# Input.net
KiCad netlist of a schematic drawn in Altium Designer
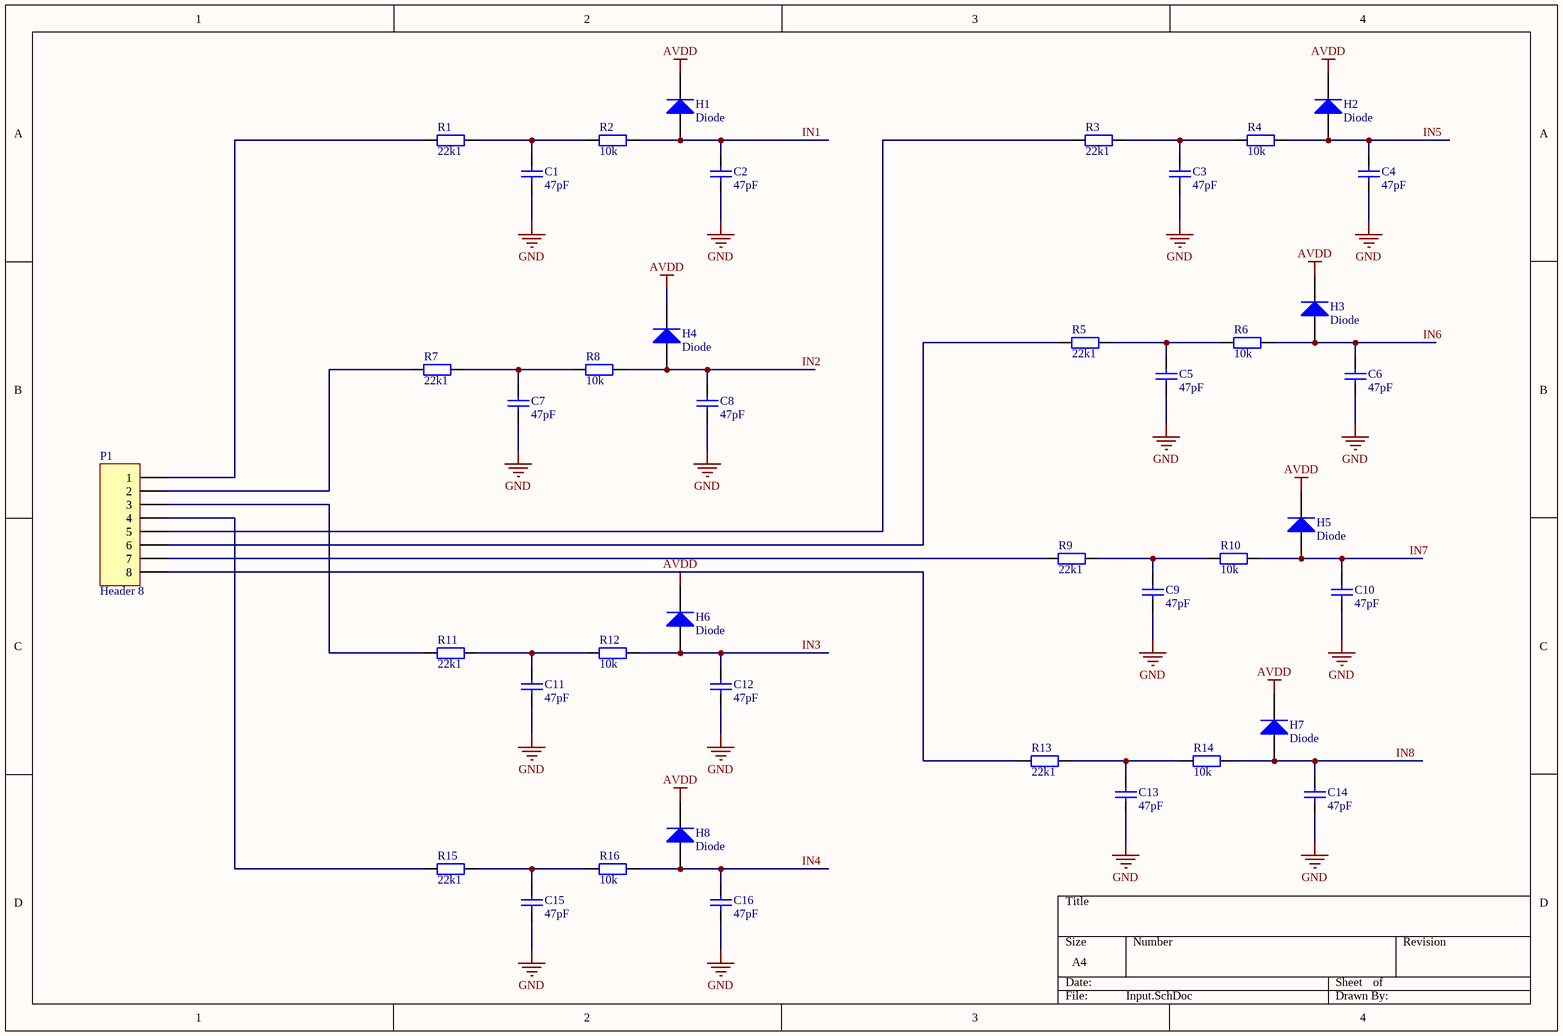
[diagram p0: Input.SchDoc]

(export (version "E")
  (design (tool "Eeschema 10.0.6"))
  (components
    (comp (ref "C1")
      (value "47pF")
      (footprint "RAD-0.3")
      (description "Capacitor")
      (fields (field (name "PUBLISHER") "Altium Limited"))
      (libsource (lib "Miscellaneous Devices") (part "Cap"))
    )
    (comp (ref "C2")
      (value "47pF")
      (footprint "RAD-0.3")
      (description "Capacitor")
      (fields (field (name "PUBLISHER") "Altium Limited"))
      (libsource (lib "Miscellaneous Devices") (part "Cap"))
    )
    (comp (ref "C3")
      (value "47pF")
      (footprint "RAD-0.3")
      (description "Capacitor")
      (fields (field (name "PUBLISHER") "Altium Limited"))
      (libsource (lib "Miscellaneous Devices") (part "Cap"))
    )
    (comp (ref "C4")
      (value "47pF")
      (footprint "RAD-0.3")
      (description "Capacitor")
      (fields (field (name "PUBLISHER") "Altium Limited"))
      (libsource (lib "Miscellaneous Devices") (part "Cap"))
    )
    (comp (ref "C5")
      (value "47pF")
      (footprint "RAD-0.3")
      (description "Capacitor")
      (fields (field (name "PUBLISHER") "Altium Limited"))
      (libsource (lib "Miscellaneous Devices") (part "Cap"))
    )
    (comp (ref "C6")
      (value "47pF")
      (footprint "RAD-0.3")
      (description "Capacitor")
      (fields (field (name "PUBLISHER") "Altium Limited"))
      (libsource (lib "Miscellaneous Devices") (part "Cap"))
    )
    (comp (ref "C7")
      (value "47pF")
      (footprint "RAD-0.3")
      (description "Capacitor")
      (fields (field (name "PUBLISHER") "Altium Limited"))
      (libsource (lib "Miscellaneous Devices") (part "Cap"))
    )
    (comp (ref "C8")
      (value "47pF")
      (footprint "RAD-0.3")
      (description "Capacitor")
      (fields (field (name "PUBLISHER") "Altium Limited"))
      (libsource (lib "Miscellaneous Devices") (part "Cap"))
    )
    (comp (ref "C9")
      (value "47pF")
      (footprint "RAD-0.3")
      (description "Capacitor")
      (fields (field (name "PUBLISHER") "Altium Limited"))
      (libsource (lib "Miscellaneous Devices") (part "Cap"))
    )
    (comp (ref "C10")
      (value "47pF")
      (footprint "RAD-0.3")
      (description "Capacitor")
      (fields (field (name "PUBLISHER") "Altium Limited"))
      (libsource (lib "Miscellaneous Devices") (part "Cap"))
    )
    (comp (ref "C11")
      (value "47pF")
      (footprint "RAD-0.3")
      (description "Capacitor")
      (fields (field (name "PUBLISHER") "Altium Limited"))
      (libsource (lib "Miscellaneous Devices") (part "Cap"))
    )
    (comp (ref "C12")
      (value "47pF")
      (footprint "RAD-0.3")
      (description "Capacitor")
      (fields (field (name "PUBLISHER") "Altium Limited"))
      (libsource (lib "Miscellaneous Devices") (part "Cap"))
    )
    (comp (ref "C13")
      (value "47pF")
      (footprint "RAD-0.3")
      (description "Capacitor")
      (fields (field (name "PUBLISHER") "Altium Limited"))
      (libsource (lib "Miscellaneous Devices") (part "Cap"))
    )
    (comp (ref "C14")
      (value "47pF")
      (footprint "RAD-0.3")
      (description "Capacitor")
      (fields (field (name "PUBLISHER") "Altium Limited"))
      (libsource (lib "Miscellaneous Devices") (part "Cap"))
    )
    (comp (ref "C15")
      (value "47pF")
      (footprint "RAD-0.3")
      (description "Capacitor")
      (fields (field (name "PUBLISHER") "Altium Limited"))
      (libsource (lib "Miscellaneous Devices") (part "Cap"))
    )
    (comp (ref "C16")
      (value "47pF")
      (footprint "RAD-0.3")
      (description "Capacitor")
      (fields (field (name "PUBLISHER") "Altium Limited"))
      (libsource (lib "Miscellaneous Devices") (part "Cap"))
    )
    (comp (ref "H1")
      (value "Diode")
      (footprint "SMC")
      (description "Default Diode")
      (fields (field (name "PUBLISHER") "Altium Limited"))
      (libsource (lib "Miscellaneous Devices") (part "Diode"))
    )
    (comp (ref "H2")
      (value "Diode")
      (footprint "SMC")
      (description "Default Diode")
      (fields (field (name "PUBLISHER") "Altium Limited"))
      (libsource (lib "Miscellaneous Devices") (part "Diode"))
    )
    (comp (ref "H3")
      (value "Diode")
      (footprint "SMC")
      (description "Default Diode")
      (fields (field (name "PUBLISHER") "Altium Limited"))
      (libsource (lib "Miscellaneous Devices") (part "Diode"))
    )
    (comp (ref "H4")
      (value "Diode")
      (footprint "SMC")
      (description "Default Diode")
      (fields (field (name "PUBLISHER") "Altium Limited"))
      (libsource (lib "Miscellaneous Devices") (part "Diode"))
    )
    (comp (ref "H5")
      (value "Diode")
      (footprint "SMC")
      (description "Default Diode")
      (fields (field (name "PUBLISHER") "Altium Limited"))
      (libsource (lib "Miscellaneous Devices") (part "Diode"))
    )
    (comp (ref "H6")
      (value "Diode")
      (footprint "SMC")
      (description "Default Diode")
      (fields (field (name "PUBLISHER") "Altium Limited"))
      (libsource (lib "Miscellaneous Devices") (part "Diode"))
    )
    (comp (ref "H7")
      (value "Diode")
      (footprint "SMC")
      (description "Default Diode")
      (fields (field (name "PUBLISHER") "Altium Limited"))
      (libsource (lib "Miscellaneous Devices") (part "Diode"))
    )
    (comp (ref "H8")
      (value "Diode")
      (footprint "SMC")
      (description "Default Diode")
      (fields (field (name "PUBLISHER") "Altium Limited"))
      (libsource (lib "Miscellaneous Devices") (part "Diode"))
    )
    (comp (ref "P1")
      (value "Header 8")
      (footprint "HDR1X8")
      (description "Header, 8-Pin")
      (fields (field (name "PUBLISHER") "Altium Limited"))
      (libsource (lib "Miscellaneous Connectors") (part "Header 8"))
    )
    (comp (ref "R1")
      (value "22k1")
      (footprint "AXIAL-0.4")
      (description "Resistor")
      (fields (field (name "PUBLISHER") "Altium Limited"))
      (libsource (lib "Miscellaneous Devices") (part "Res2"))
    )
    (comp (ref "R2")
      (value "10k")
      (footprint "AXIAL-0.4")
      (description "Resistor")
      (fields (field (name "PUBLISHER") "Altium Limited"))
      (libsource (lib "Miscellaneous Devices") (part "Res2"))
    )
    (comp (ref "R3")
      (value "22k1")
      (footprint "AXIAL-0.4")
      (description "Resistor")
      (fields (field (name "PUBLISHER") "Altium Limited"))
      (libsource (lib "Miscellaneous Devices") (part "Res2"))
    )
    (comp (ref "R4")
      (value "10k")
      (footprint "AXIAL-0.4")
      (description "Resistor")
      (fields (field (name "PUBLISHER") "Altium Limited"))
      (libsource (lib "Miscellaneous Devices") (part "Res2"))
    )
    (comp (ref "R5")
      (value "22k1")
      (footprint "AXIAL-0.4")
      (description "Resistor")
      (fields (field (name "PUBLISHER") "Altium Limited"))
      (libsource (lib "Miscellaneous Devices") (part "Res2"))
    )
    (comp (ref "R6")
      (value "10k")
      (footprint "AXIAL-0.4")
      (description "Resistor")
      (fields (field (name "PUBLISHER") "Altium Limited"))
      (libsource (lib "Miscellaneous Devices") (part "Res2"))
    )
    (comp (ref "R7")
      (value "22k1")
      (footprint "AXIAL-0.4")
      (description "Resistor")
      (fields (field (name "PUBLISHER") "Altium Limited"))
      (libsource (lib "Miscellaneous Devices") (part "Res2"))
    )
    (comp (ref "R8")
      (value "10k")
      (footprint "AXIAL-0.4")
      (description "Resistor")
      (fields (field (name "PUBLISHER") "Altium Limited"))
      (libsource (lib "Miscellaneous Devices") (part "Res2"))
    )
    (comp (ref "R9")
      (value "22k1")
      (footprint "AXIAL-0.4")
      (description "Resistor")
      (fields (field (name "PUBLISHER") "Altium Limited"))
      (libsource (lib "Miscellaneous Devices") (part "Res2"))
    )
    (comp (ref "R10")
      (value "10k")
      (footprint "AXIAL-0.4")
      (description "Resistor")
      (fields (field (name "PUBLISHER") "Altium Limited"))
      (libsource (lib "Miscellaneous Devices") (part "Res2"))
    )
    (comp (ref "R11")
      (value "22k1")
      (footprint "AXIAL-0.4")
      (description "Resistor")
      (fields (field (name "PUBLISHER") "Altium Limited"))
      (libsource (lib "Miscellaneous Devices") (part "Res2"))
    )
    (comp (ref "R12")
      (value "10k")
      (footprint "AXIAL-0.4")
      (description "Resistor")
      (fields (field (name "PUBLISHER") "Altium Limited"))
      (libsource (lib "Miscellaneous Devices") (part "Res2"))
    )
    (comp (ref "R13")
      (value "22k1")
      (footprint "AXIAL-0.4")
      (description "Resistor")
      (fields (field (name "PUBLISHER") "Altium Limited"))
      (libsource (lib "Miscellaneous Devices") (part "Res2"))
    )
    (comp (ref "R14")
      (value "10k")
      (footprint "AXIAL-0.4")
      (description "Resistor")
      (fields (field (name "PUBLISHER") "Altium Limited"))
      (libsource (lib "Miscellaneous Devices") (part "Res2"))
    )
    (comp (ref "R15")
      (value "22k1")
      (footprint "AXIAL-0.4")
      (description "Resistor")
      (fields (field (name "PUBLISHER") "Altium Limited"))
      (libsource (lib "Miscellaneous Devices") (part "Res2"))
    )
    (comp (ref "R16")
      (value "10k")
      (footprint "AXIAL-0.4")
      (description "Resistor")
      (fields (field (name "PUBLISHER") "Altium Limited"))
      (libsource (lib "Miscellaneous Devices") (part "Res2"))
    )
  )
  (nets
    (net (code "1") (name "/IN1") (class "Default")
      (node (ref "C2") (pin "2") (pinfunction "2_2") (pintype "passive"))
      (node (ref "H1") (pin "1") (pinfunction "A_1") (pintype "passive"))
      (node (ref "R2") (pin "2") (pinfunction "2_2") (pintype "passive"))
    )
    (net (code "2") (name "/IN2") (class "Default")
      (node (ref "C8") (pin "2") (pinfunction "2_2") (pintype "passive"))
      (node (ref "H4") (pin "1") (pinfunction "A_1") (pintype "passive"))
      (node (ref "R8") (pin "2") (pinfunction "2_2") (pintype "passive"))
    )
    (net (code "3") (name "/IN3") (class "Default")
      (node (ref "C12") (pin "2") (pinfunction "2_2") (pintype "passive"))
      (node (ref "H6") (pin "1") (pinfunction "A_1") (pintype "passive"))
      (node (ref "R12") (pin "2") (pinfunction "2_2") (pintype "passive"))
    )
    (net (code "4") (name "/IN4") (class "Default")
      (node (ref "C16") (pin "2") (pinfunction "2_2") (pintype "passive"))
      (node (ref "H8") (pin "1") (pinfunction "A_1") (pintype "passive"))
      (node (ref "R16") (pin "2") (pinfunction "2_2") (pintype "passive"))
    )
    (net (code "5") (name "/IN5") (class "Default")
      (node (ref "C4") (pin "2") (pinfunction "2_2") (pintype "passive"))
      (node (ref "H2") (pin "1") (pinfunction "A_1") (pintype "passive"))
      (node (ref "R4") (pin "2") (pinfunction "2_2") (pintype "passive"))
    )
    (net (code "6") (name "/IN6") (class "Default")
      (node (ref "C6") (pin "2") (pinfunction "2_2") (pintype "passive"))
      (node (ref "H3") (pin "1") (pinfunction "A_1") (pintype "passive"))
      (node (ref "R6") (pin "2") (pinfunction "2_2") (pintype "passive"))
    )
    (net (code "7") (name "/IN7") (class "Default")
      (node (ref "C10") (pin "2") (pinfunction "2_2") (pintype "passive"))
      (node (ref "H5") (pin "1") (pinfunction "A_1") (pintype "passive"))
      (node (ref "R10") (pin "2") (pinfunction "2_2") (pintype "passive"))
    )
    (net (code "8") (name "/IN8") (class "Default")
      (node (ref "C14") (pin "2") (pinfunction "2_2") (pintype "passive"))
      (node (ref "H7") (pin "1") (pinfunction "A_1") (pintype "passive"))
      (node (ref "R14") (pin "2") (pinfunction "2_2") (pintype "passive"))
    )
    (net (code "9") (name "AVDD") (class "Default")
      (node (ref "H1") (pin "2") (pinfunction "K_2") (pintype "passive"))
      (node (ref "H2") (pin "2") (pinfunction "K_2") (pintype "passive"))
      (node (ref "H3") (pin "2") (pinfunction "K_2") (pintype "passive"))
      (node (ref "H4") (pin "2") (pinfunction "K_2") (pintype "passive"))
      (node (ref "H5") (pin "2") (pinfunction "K_2") (pintype "passive"))
      (node (ref "H6") (pin "2") (pinfunction "K_2") (pintype "passive"))
      (node (ref "H7") (pin "2") (pinfunction "K_2") (pintype "passive"))
      (node (ref "H8") (pin "2") (pinfunction "K_2") (pintype "passive"))
    )
    (net (code "10") (name "GND") (class "Default")
      (node (ref "C1") (pin "1") (pinfunction "1_1") (pintype "passive"))
      (node (ref "C10") (pin "1") (pinfunction "1_1") (pintype "passive"))
      (node (ref "C11") (pin "1") (pinfunction "1_1") (pintype "passive"))
      (node (ref "C12") (pin "1") (pinfunction "1_1") (pintype "passive"))
      (node (ref "C13") (pin "1") (pinfunction "1_1") (pintype "passive"))
      (node (ref "C14") (pin "1") (pinfunction "1_1") (pintype "passive"))
      (node (ref "C15") (pin "1") (pinfunction "1_1") (pintype "passive"))
      (node (ref "C16") (pin "1") (pinfunction "1_1") (pintype "passive"))
      (node (ref "C2") (pin "1") (pinfunction "1_1") (pintype "passive"))
      (node (ref "C3") (pin "1") (pinfunction "1_1") (pintype "passive"))
      (node (ref "C4") (pin "1") (pinfunction "1_1") (pintype "passive"))
      (node (ref "C5") (pin "1") (pinfunction "1_1") (pintype "passive"))
      (node (ref "C6") (pin "1") (pinfunction "1_1") (pintype "passive"))
      (node (ref "C7") (pin "1") (pinfunction "1_1") (pintype "passive"))
      (node (ref "C8") (pin "1") (pinfunction "1_1") (pintype "passive"))
      (node (ref "C9") (pin "1") (pinfunction "1_1") (pintype "passive"))
    )
    (net (code "11") (name "Net-(C1-Pad2)") (class "Default")
      (node (ref "C1") (pin "2") (pinfunction "2_2") (pintype "passive"))
      (node (ref "R1") (pin "2") (pinfunction "2_2") (pintype "passive"))
      (node (ref "R2") (pin "1") (pinfunction "1_1") (pintype "passive"))
    )
    (net (code "12") (name "Net-(C3-Pad2)") (class "Default")
      (node (ref "C3") (pin "2") (pinfunction "2_2") (pintype "passive"))
      (node (ref "R3") (pin "2") (pinfunction "2_2") (pintype "passive"))
      (node (ref "R4") (pin "1") (pinfunction "1_1") (pintype "passive"))
    )
    (net (code "13") (name "Net-(C5-Pad2)") (class "Default")
      (node (ref "C5") (pin "2") (pinfunction "2_2") (pintype "passive"))
      (node (ref "R5") (pin "2") (pinfunction "2_2") (pintype "passive"))
      (node (ref "R6") (pin "1") (pinfunction "1_1") (pintype "passive"))
    )
    (net (code "14") (name "Net-(C7-Pad2)") (class "Default")
      (node (ref "C7") (pin "2") (pinfunction "2_2") (pintype "passive"))
      (node (ref "R7") (pin "2") (pinfunction "2_2") (pintype "passive"))
      (node (ref "R8") (pin "1") (pinfunction "1_1") (pintype "passive"))
    )
    (net (code "15") (name "Net-(C9-Pad2)") (class "Default")
      (node (ref "C9") (pin "2") (pinfunction "2_2") (pintype "passive"))
      (node (ref "R10") (pin "1") (pinfunction "1_1") (pintype "passive"))
      (node (ref "R9") (pin "2") (pinfunction "2_2") (pintype "passive"))
    )
    (net (code "16") (name "Net-(C11-Pad2)") (class "Default")
      (node (ref "C11") (pin "2") (pinfunction "2_2") (pintype "passive"))
      (node (ref "R11") (pin "2") (pinfunction "2_2") (pintype "passive"))
      (node (ref "R12") (pin "1") (pinfunction "1_1") (pintype "passive"))
    )
    (net (code "17") (name "Net-(C13-Pad2)") (class "Default")
      (node (ref "C13") (pin "2") (pinfunction "2_2") (pintype "passive"))
      (node (ref "R13") (pin "2") (pinfunction "2_2") (pintype "passive"))
      (node (ref "R14") (pin "1") (pinfunction "1_1") (pintype "passive"))
    )
    (net (code "18") (name "Net-(C15-Pad2)") (class "Default")
      (node (ref "C15") (pin "2") (pinfunction "2_2") (pintype "passive"))
      (node (ref "R15") (pin "2") (pinfunction "2_2") (pintype "passive"))
      (node (ref "R16") (pin "1") (pinfunction "1_1") (pintype "passive"))
    )
    (net (code "19") (name "Net-(P1-Pad1)") (class "Default")
      (node (ref "P1") (pin "1") (pinfunction "1_1") (pintype "passive"))
      (node (ref "R1") (pin "1") (pinfunction "1_1") (pintype "passive"))
    )
    (net (code "20") (name "Net-(P1-Pad2)") (class "Default")
      (node (ref "P1") (pin "2") (pinfunction "2_2") (pintype "passive"))
      (node (ref "R7") (pin "1") (pinfunction "1_1") (pintype "passive"))
    )
    (net (code "21") (name "Net-(P1-Pad3)") (class "Default")
      (node (ref "P1") (pin "3") (pinfunction "3_3") (pintype "passive"))
      (node (ref "R11") (pin "1") (pinfunction "1_1") (pintype "passive"))
    )
    (net (code "22") (name "Net-(P1-Pad4)") (class "Default")
      (node (ref "P1") (pin "4") (pinfunction "4_4") (pintype "passive"))
      (node (ref "R15") (pin "1") (pinfunction "1_1") (pintype "passive"))
    )
    (net (code "23") (name "Net-(P1-Pad5)") (class "Default")
      (node (ref "P1") (pin "5") (pinfunction "5_5") (pintype "passive"))
      (node (ref "R3") (pin "1") (pinfunction "1_1") (pintype "passive"))
    )
    (net (code "24") (name "Net-(P1-Pad6)") (class "Default")
      (node (ref "P1") (pin "6") (pinfunction "6_6") (pintype "passive"))
      (node (ref "R5") (pin "1") (pinfunction "1_1") (pintype "passive"))
    )
    (net (code "25") (name "Net-(P1-Pad7)") (class "Default")
      (node (ref "P1") (pin "7") (pinfunction "7_7") (pintype "passive"))
      (node (ref "R9") (pin "1") (pinfunction "1_1") (pintype "passive"))
    )
    (net (code "26") (name "Net-(P1-Pad8)") (class "Default")
      (node (ref "P1") (pin "8") (pinfunction "8_8") (pintype "passive"))
      (node (ref "R13") (pin "1") (pinfunction "1_1") (pintype "passive"))
    )
  )
)
